# luci2_device_revA.net
KiCad netlist of a schematic drawn in EAGLE
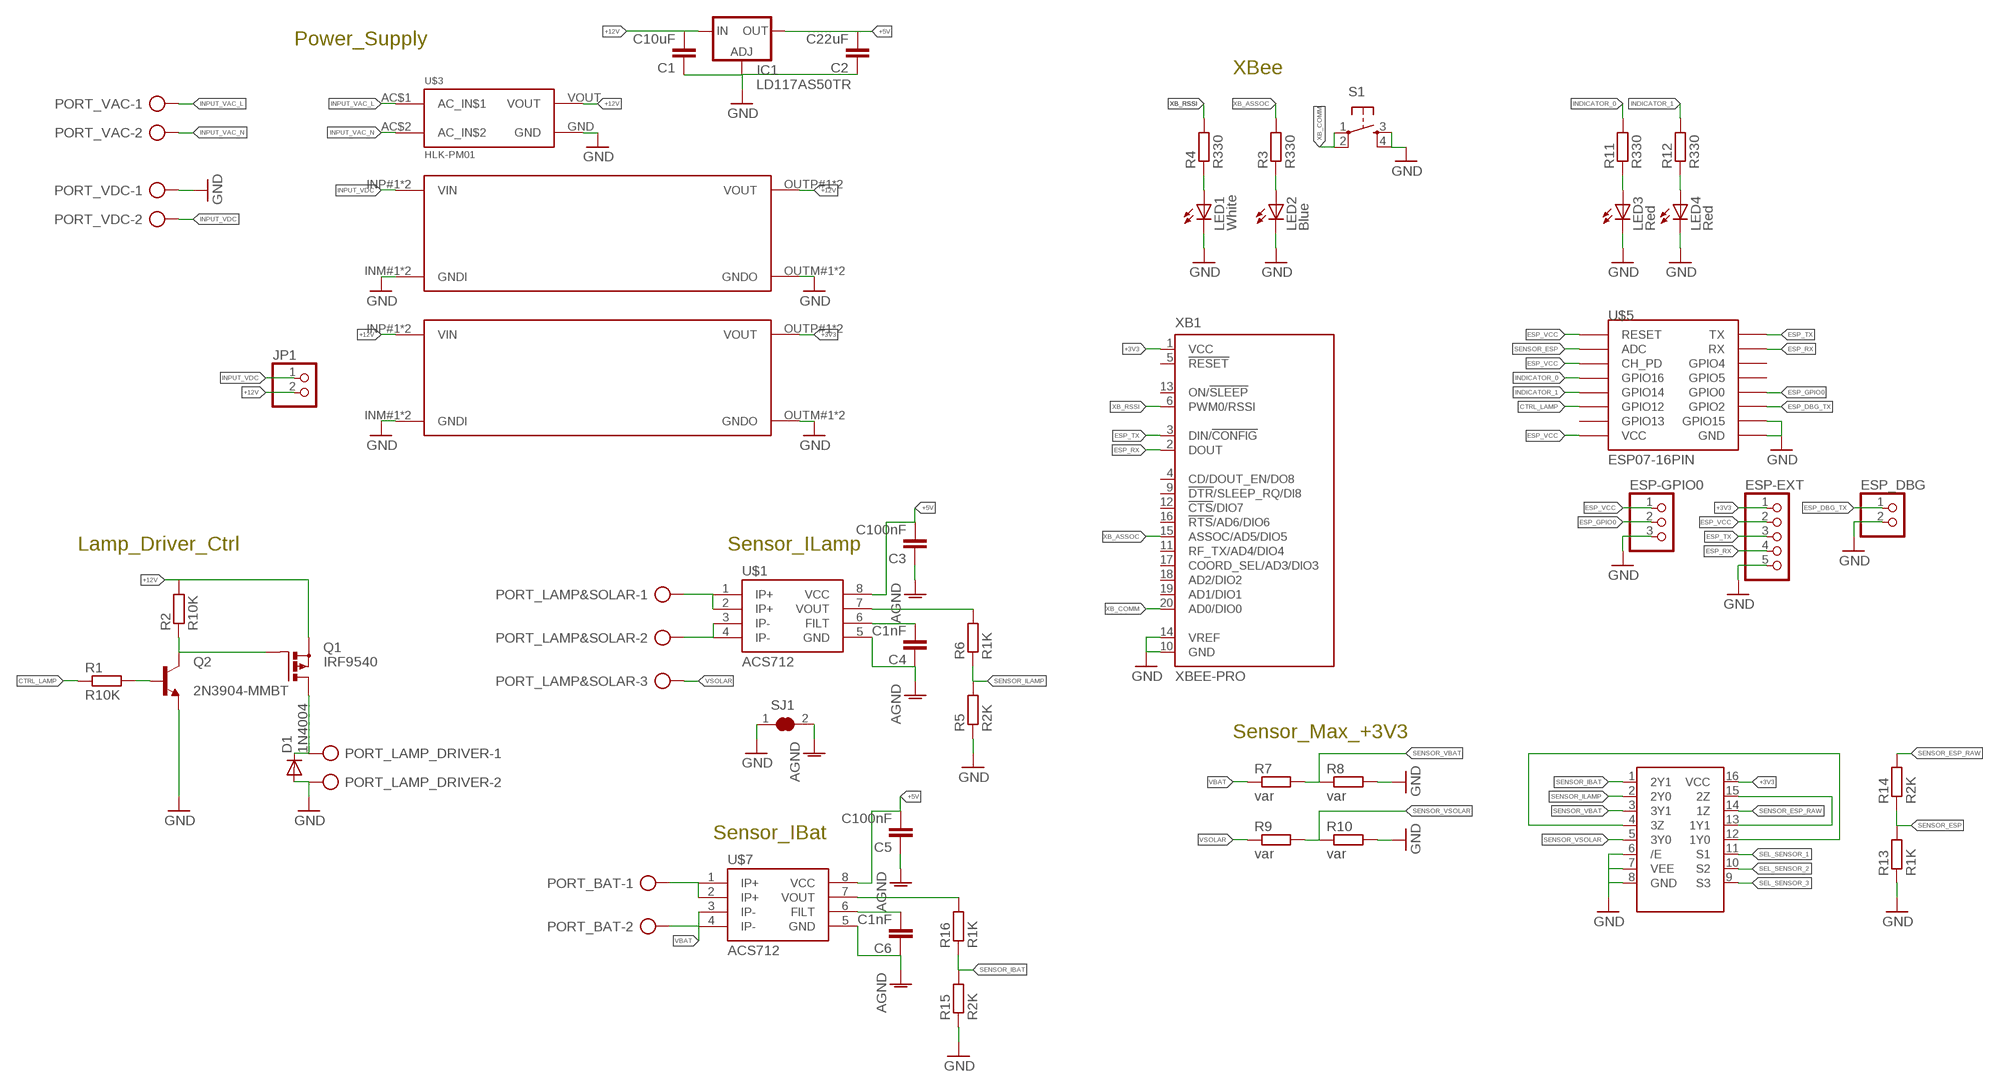
[diagram p0: schematic, sheet 1]

(export (version "E")
  (design (tool "Eeschema 10.0.6"))
  (components
    (comp (ref "C1")
      (value "C10uF")
      (footprint "eagle-import:C0805")
      (libsource (lib "eagle-import") (part "C-EUC0805"))
    )
    (comp (ref "C2")
      (value "C22uF")
      (footprint "eagle-import:C0805")
      (libsource (lib "eagle-import") (part "C-EUC0805"))
    )
    (comp (ref "C3")
      (value "C100nF")
      (footprint "eagle-import:C0805")
      (libsource (lib "eagle-import") (part "C-EUC0805"))
    )
    (comp (ref "C4")
      (value "C1nF")
      (footprint "eagle-import:C0805")
      (libsource (lib "eagle-import") (part "C-EUC0805"))
    )
    (comp (ref "C5")
      (value "C100nF")
      (footprint "eagle-import:C0805")
      (libsource (lib "eagle-import") (part "C-EUC0805"))
    )
    (comp (ref "C6")
      (value "C1nF")
      (footprint "eagle-import:C0805")
      (libsource (lib "eagle-import") (part "C-EUC0805"))
    )
    (comp (ref "D1")
      (value "1N4004")
      (footprint "eagle-import:DO41-10")
      (libsource (lib "eagle-import") (part "1N4004"))
    )
    (comp (ref "ESP-EXT")
      (value "HEADER-1X5ROUND")
      (footprint "eagle-import:1X05_ROUND")
      (libsource (lib "eagle-import") (part "HEADER-1X5ROUND"))
    )
    (comp (ref "ESP-GPIO0")
      (value "HEADER-1X3ROUND")
      (footprint "eagle-import:1X03_ROUND")
      (libsource (lib "eagle-import") (part "HEADER-1X3ROUND"))
    )
    (comp (ref "ESP_DBG")
      (value "HEADER-1X2ROUND")
      (footprint "eagle-import:1X02_ROUND")
      (libsource (lib "eagle-import") (part "HEADER-1X2ROUND"))
    )
    (comp (ref "IC1")
      (value "LD117AS50TR")
      (footprint "eagle-import:SOT223")
      (libsource (lib "eagle-import") (part "LD117A?S50TR"))
    )
    (comp (ref "JP1")
      (value "HEADER-1X2ROUND")
      (footprint "eagle-import:1X02_ROUND")
      (libsource (lib "eagle-import") (part "HEADER-1X2ROUND"))
    )
    (comp (ref "LED1")
      (value "White")
      (footprint "eagle-import:CHIPLED_0805")
      (libsource (lib "eagle-import") (part "LEDCHIPLED_0805"))
    )
    (comp (ref "LED2")
      (value "Blue")
      (footprint "eagle-import:CHIPLED_0805")
      (libsource (lib "eagle-import") (part "LEDCHIPLED_0805"))
    )
    (comp (ref "LED3")
      (value "Red")
      (footprint "eagle-import:CHIPLED_0805")
      (libsource (lib "eagle-import") (part "LEDCHIPLED_0805"))
    )
    (comp (ref "LED4")
      (value "Red")
      (footprint "eagle-import:CHIPLED_0805")
      (libsource (lib "eagle-import") (part "LEDCHIPLED_0805"))
    )
    (comp (ref "PORT_BAT")
      (value "AK300/2")
      (footprint "eagle-import:AK300_2")
      (libsource (lib "eagle-import") (part "AK300/2"))
    )
    (comp (ref "PORT_LAMP&SOLAR")
      (value "AK300/3")
      (footprint "eagle-import:AK300_3")
      (libsource (lib "eagle-import") (part "AK300/3"))
    )
    (comp (ref "PORT_LAMP_DRIVER")
      (value "AK300/2")
      (footprint "eagle-import:AK300_2")
      (libsource (lib "eagle-import") (part "AK300/2"))
    )
    (comp (ref "PORT_VAC")
      (value "AK300/2")
      (footprint "eagle-import:AK300_2")
      (libsource (lib "eagle-import") (part "AK300/2"))
    )
    (comp (ref "PORT_VDC")
      (value "AK300/2")
      (footprint "eagle-import:AK300_2")
      (libsource (lib "eagle-import") (part "AK300/2"))
    )
    (comp (ref "Q1")
      (value "IRF9540")
      (footprint "eagle-import:TO220BV")
      (libsource (lib "eagle-import") (part "PMOSFET_PTO220BV"))
    )
    (comp (ref "Q2")
      (value "2N3904-MMBT")
      (footprint "eagle-import:SOT23")
      (libsource (lib "eagle-import") (part "2N3904-MMBT"))
    )
    (comp (ref "R1")
      (value "R10K")
      (footprint "eagle-import:M0805")
      (libsource (lib "eagle-import") (part "R-EU_M0805"))
    )
    (comp (ref "R2")
      (value "R10K")
      (footprint "eagle-import:M0805")
      (libsource (lib "eagle-import") (part "R-EU_M0805"))
    )
    (comp (ref "R3")
      (value "R330")
      (footprint "eagle-import:M0805")
      (libsource (lib "eagle-import") (part "R-EU_M0805"))
    )
    (comp (ref "R4")
      (value "R330")
      (footprint "eagle-import:M0805")
      (libsource (lib "eagle-import") (part "R-EU_M0805"))
    )
    (comp (ref "R5")
      (value "R2K")
      (footprint "eagle-import:M0805")
      (libsource (lib "eagle-import") (part "R-EU_M0805"))
    )
    (comp (ref "R6")
      (value "R1K")
      (footprint "eagle-import:M0805")
      (libsource (lib "eagle-import") (part "R-EU_M0805"))
    )
    (comp (ref "R7")
      (value "var")
      (footprint "eagle-import:M0805")
      (libsource (lib "eagle-import") (part "R-EU_M0805"))
    )
    (comp (ref "R8")
      (value "var")
      (footprint "eagle-import:M0805")
      (libsource (lib "eagle-import") (part "R-EU_M0805"))
    )
    (comp (ref "R9")
      (value "var")
      (footprint "eagle-import:M0805")
      (libsource (lib "eagle-import") (part "R-EU_M0805"))
    )
    (comp (ref "R10")
      (value "var")
      (footprint "eagle-import:M0805")
      (libsource (lib "eagle-import") (part "R-EU_M0805"))
    )
    (comp (ref "R11")
      (value "R330")
      (footprint "eagle-import:M0805")
      (libsource (lib "eagle-import") (part "R-EU_M0805"))
    )
    (comp (ref "R12")
      (value "R330")
      (footprint "eagle-import:M0805")
      (libsource (lib "eagle-import") (part "R-EU_M0805"))
    )
    (comp (ref "R13")
      (value "R1K")
      (footprint "eagle-import:M0805")
      (libsource (lib "eagle-import") (part "R-EU_M0805"))
    )
    (comp (ref "R14")
      (value "R2K")
      (footprint "eagle-import:M0805")
      (libsource (lib "eagle-import") (part "R-EU_M0805"))
    )
    (comp (ref "R15")
      (value "R2K")
      (footprint "eagle-import:M0805")
      (libsource (lib "eagle-import") (part "R-EU_M0805"))
    )
    (comp (ref "R16")
      (value "R1K")
      (footprint "eagle-import:M0805")
      (libsource (lib "eagle-import") (part "R-EU_M0805"))
    )
    (comp (ref "S1")
      (value "TAC_SWITCHPTH")
      (footprint "eagle-import:TACTILE-PTH")
      (libsource (lib "eagle-import") (part "TAC_SWITCHPTH"))
    )
    (comp (ref "SJ1")
      (value "SOLDERJUMPER_CLOSED")
      (footprint "eagle-import:SOLDERJUMPER_CLOSEDWIRE")
      (libsource (lib "eagle-import") (part "SOLDERJUMPER_CLOSED"))
    )
    (comp (ref "U$1")
      (value "ACS712")
      (footprint "eagle-import:SO08")
      (libsource (lib "eagle-import") (part "ACS712"))
    )
    (comp (ref "U$2")
      (value "DCDCMODULE_SMALL")
      (footprint "eagle-import:DCDCMODULE-SMALL")
      (libsource (lib "eagle-import") (part "DCDCMODULE_SMALL"))
    )
    (comp (ref "U$3")
      (value "HLK-PM01")
      (footprint "eagle-import:HLK-PM01")
      (libsource (lib "eagle-import") (part "HLK-PM01"))
    )
    (comp (ref "U$4")
      (value "DCDCMODULE_SMALL")
      (footprint "eagle-import:DCDCMODULE-SMALL")
      (libsource (lib "eagle-import") (part "DCDCMODULE_SMALL"))
    )
    (comp (ref "U$5")
      (value "ESP07-16PIN")
      (footprint "eagle-import:ESP07-16PIN")
      (libsource (lib "eagle-import") (part "ESP07-16PIN"))
    )
    (comp (ref "U$6")
      (value "74HC4053D")
      (footprint "eagle-import:SO16")
      (libsource (lib "eagle-import") (part "74HC4053D"))
    )
    (comp (ref "U$7")
      (value "ACS712")
      (footprint "eagle-import:SO08")
      (libsource (lib "eagle-import") (part "ACS712"))
    )
    (comp (ref "XB1")
      (value "XBEE-PRO")
      (footprint "eagle-import:XBEE-PRO")
      (libsource (lib "eagle-import") (part "XBEE-PRO"))
    )
  )
  (nets
    (net (code "1") (name "+3V3") (class "Default")
      (node (ref "ESP-EXT") (pin "1") (pinfunction "1_1") (pintype "passive"))
      (node (ref "U$2") (pin "OUTP#1") (pinfunction "VOUT_OUTP#1") (pintype "bidirectional"))
      (node (ref "U$2") (pin "OUTP#2") (pinfunction "VOUT_OUTP#2") (pintype "bidirectional"))
      (node (ref "U$6") (pin "16") (pinfunction "VCC_16") (pintype "bidirectional"))
      (node (ref "XB1") (pin "1") (pinfunction "VCC_1") (pintype "power_in"))
    )
    (net (code "2") (name "+5V") (class "Default")
      (node (ref "C2") (pin "2") (pinfunction "2_2") (pintype "passive"))
      (node (ref "C3") (pin "2") (pinfunction "2_2") (pintype "passive"))
      (node (ref "C5") (pin "2") (pinfunction "2_2") (pintype "passive"))
      (node (ref "IC1") (pin "4") (pinfunction "OUT_4") (pintype "passive"))
      (node (ref "U$1") (pin "8") (pinfunction "VCC_8") (pintype "bidirectional"))
      (node (ref "U$7") (pin "8") (pinfunction "VCC_8") (pintype "bidirectional"))
    )
    (net (code "3") (name "+12V") (class "Default")
      (node (ref "C1") (pin "2") (pinfunction "2_2") (pintype "passive"))
      (node (ref "IC1") (pin "3") (pinfunction "IN_3") (pintype "input"))
      (node (ref "JP1") (pin "2") (pinfunction "2_2") (pintype "passive"))
      (node (ref "Q1") (pin "S") (pinfunction "S_S") (pintype "passive"))
      (node (ref "R2") (pin "2") (pinfunction "2_2") (pintype "passive"))
      (node (ref "U$2") (pin "INP#1") (pinfunction "VIN_INP#1") (pintype "bidirectional"))
      (node (ref "U$2") (pin "INP#2") (pinfunction "VIN_INP#2") (pintype "bidirectional"))
      (node (ref "U$3") (pin "VOUT") (pinfunction "VOUT_VOUT") (pintype "bidirectional"))
      (node (ref "U$4") (pin "OUTP#1") (pinfunction "VOUT_OUTP#1") (pintype "bidirectional"))
      (node (ref "U$4") (pin "OUTP#2") (pinfunction "VOUT_OUTP#2") (pintype "bidirectional"))
    )
    (net (code "4") (name "AGND") (class "Default")
      (node (ref "C3") (pin "1") (pinfunction "1_1") (pintype "passive"))
      (node (ref "C4") (pin "1") (pinfunction "1_1") (pintype "passive"))
      (node (ref "C5") (pin "1") (pinfunction "1_1") (pintype "passive"))
      (node (ref "C6") (pin "1") (pinfunction "1_1") (pintype "passive"))
      (node (ref "SJ1") (pin "2") (pinfunction "2_2") (pintype "passive"))
      (node (ref "U$1") (pin "5") (pinfunction "GND_5") (pintype "bidirectional"))
      (node (ref "U$7") (pin "5") (pinfunction "GND_5") (pintype "bidirectional"))
    )
    (net (code "5") (name "CTRL_LAMP") (class "Default")
      (node (ref "R1") (pin "1") (pinfunction "1_1") (pintype "passive"))
      (node (ref "U$5") (pin "GPIO12") (pinfunction "GPIO12_GPIO12") (pintype "bidirectional"))
    )
    (net (code "6") (name "ESP_DBG_TX") (class "Default")
      (node (ref "ESP_DBG") (pin "1") (pinfunction "1_1") (pintype "passive"))
      (node (ref "U$5") (pin "GPIO2") (pinfunction "GPIO2_GPIO2") (pintype "bidirectional"))
    )
    (net (code "7") (name "ESP_GPIO0") (class "Default")
      (node (ref "ESP-GPIO0") (pin "2") (pinfunction "2_2") (pintype "passive"))
      (node (ref "U$5") (pin "GPIO0") (pinfunction "GPIO0_GPIO0") (pintype "bidirectional"))
    )
    (net (code "8") (name "ESP_RX") (class "Default")
      (node (ref "ESP-EXT") (pin "4") (pinfunction "4_4") (pintype "passive"))
      (node (ref "U$5") (pin "RX") (pinfunction "RX_RX") (pintype "bidirectional"))
      (node (ref "XB1") (pin "2") (pinfunction "DOUT_2") (pintype "output"))
    )
    (net (code "9") (name "ESP_TX") (class "Default")
      (node (ref "ESP-EXT") (pin "3") (pinfunction "3_3") (pintype "passive"))
      (node (ref "U$5") (pin "TX") (pinfunction "TX_TX") (pintype "bidirectional"))
      (node (ref "XB1") (pin "3") (pinfunction "DIN/~{CONFIG}_3") (pintype "input"))
    )
    (net (code "10") (name "ESP_VCC") (class "Default")
      (node (ref "ESP-EXT") (pin "2") (pinfunction "2_2") (pintype "passive"))
      (node (ref "ESP-GPIO0") (pin "1") (pinfunction "1_1") (pintype "passive"))
      (node (ref "U$5") (pin "CH_PD") (pinfunction "CH_PD_CH_PD") (pintype "bidirectional"))
      (node (ref "U$5") (pin "REST") (pinfunction "RESET_REST") (pintype "bidirectional"))
      (node (ref "U$5") (pin "VCC") (pinfunction "VCC_VCC") (pintype "bidirectional"))
    )
    (net (code "11") (name "GND") (class "Default")
      (node (ref "C1") (pin "1") (pinfunction "1_1") (pintype "passive"))
      (node (ref "C2") (pin "1") (pinfunction "1_1") (pintype "passive"))
      (node (ref "D1") (pin "A") (pinfunction "A_A") (pintype "passive"))
      (node (ref "ESP-EXT") (pin "5") (pinfunction "5_5") (pintype "passive"))
      (node (ref "ESP-GPIO0") (pin "3") (pinfunction "3_3") (pintype "passive"))
      (node (ref "ESP_DBG") (pin "2") (pinfunction "2_2") (pintype "passive"))
      (node (ref "IC1") (pin "1") (pinfunction "ADJ_1") (pintype "input"))
      (node (ref "LED1") (pin "C") (pinfunction "C_C") (pintype "passive"))
      (node (ref "LED2") (pin "C") (pinfunction "C_C") (pintype "passive"))
      (node (ref "LED3") (pin "C") (pinfunction "C_C") (pintype "passive"))
      (node (ref "LED4") (pin "C") (pinfunction "C_C") (pintype "passive"))
      (node (ref "PORT_LAMP_DRIVER") (pin "2") (pinfunction "KL_2") (pintype "passive"))
      (node (ref "PORT_VDC") (pin "1") (pinfunction "KL_1") (pintype "passive"))
      (node (ref "Q2") (pin "2") (pinfunction "E_2") (pintype "passive"))
      (node (ref "R10") (pin "2") (pinfunction "2_2") (pintype "passive"))
      (node (ref "R13") (pin "1") (pinfunction "1_1") (pintype "passive"))
      (node (ref "R15") (pin "1") (pinfunction "1_1") (pintype "passive"))
      (node (ref "R5") (pin "1") (pinfunction "1_1") (pintype "passive"))
      (node (ref "R8") (pin "2") (pinfunction "2_2") (pintype "passive"))
      (node (ref "S1") (pin "3") (pinfunction "3_3") (pintype "passive"))
      (node (ref "S1") (pin "4") (pinfunction "4_4") (pintype "passive"))
      (node (ref "SJ1") (pin "1") (pinfunction "1_1") (pintype "passive"))
      (node (ref "U$2") (pin "INM#1") (pinfunction "GNDI_INM#1") (pintype "bidirectional"))
      (node (ref "U$2") (pin "INM#2") (pinfunction "GNDI_INM#2") (pintype "bidirectional"))
      (node (ref "U$2") (pin "OUTM#1") (pinfunction "GNDO_OUTM#1") (pintype "bidirectional"))
      (node (ref "U$2") (pin "OUTM#2") (pinfunction "GNDO_OUTM#2") (pintype "bidirectional"))
      (node (ref "U$3") (pin "GND") (pinfunction "GND_GND") (pintype "bidirectional"))
      (node (ref "U$4") (pin "INM#1") (pinfunction "GNDI_INM#1") (pintype "bidirectional"))
      (node (ref "U$4") (pin "INM#2") (pinfunction "GNDI_INM#2") (pintype "bidirectional"))
      (node (ref "U$4") (pin "OUTM#1") (pinfunction "GNDO_OUTM#1") (pintype "bidirectional"))
      (node (ref "U$4") (pin "OUTM#2") (pinfunction "GNDO_OUTM#2") (pintype "bidirectional"))
      (node (ref "U$5") (pin "GND") (pinfunction "GND_GND") (pintype "bidirectional"))
      (node (ref "U$5") (pin "GPIO15") (pinfunction "GPIO15_GPIO15") (pintype "bidirectional"))
      (node (ref "U$6") (pin "6") (pinfunction "/E_6") (pintype "bidirectional"))
      (node (ref "U$6") (pin "7") (pinfunction "VEE_7") (pintype "bidirectional"))
      (node (ref "U$6") (pin "8") (pinfunction "GND_8") (pintype "bidirectional"))
      (node (ref "XB1") (pin "10") (pinfunction "GND_10") (pintype "power_in"))
      (node (ref "XB1") (pin "14") (pinfunction "VREF_14") (pintype "input"))
    )
    (net (code "12") (name "INDICATOR_0") (class "Default")
      (node (ref "R11") (pin "2") (pinfunction "2_2") (pintype "passive"))
      (node (ref "U$5") (pin "GPIO16") (pinfunction "GPIO16_GPIO16") (pintype "bidirectional"))
    )
    (net (code "13") (name "INDICATOR_1") (class "Default")
      (node (ref "R12") (pin "2") (pinfunction "2_2") (pintype "passive"))
      (node (ref "U$5") (pin "GPIO14") (pinfunction "GPIO14_GPIO14") (pintype "bidirectional"))
    )
    (net (code "14") (name "INPUT_VAC_L") (class "Default")
      (node (ref "PORT_VAC") (pin "1") (pinfunction "KL_1") (pintype "passive"))
      (node (ref "U$3") (pin "AC$1") (pinfunction "AC_IN$1_AC$1") (pintype "bidirectional"))
    )
    (net (code "15") (name "INPUT_VAC_N") (class "Default")
      (node (ref "PORT_VAC") (pin "2") (pinfunction "KL_2") (pintype "passive"))
      (node (ref "U$3") (pin "AC$2") (pinfunction "AC_IN$2_AC$2") (pintype "bidirectional"))
    )
    (net (code "16") (name "INPUT_VDC") (class "Default")
      (node (ref "JP1") (pin "1") (pinfunction "1_1") (pintype "passive"))
      (node (ref "PORT_VDC") (pin "2") (pinfunction "KL_2") (pintype "passive"))
      (node (ref "U$4") (pin "INP#1") (pinfunction "VIN_INP#1") (pintype "bidirectional"))
      (node (ref "U$4") (pin "INP#2") (pinfunction "VIN_INP#2") (pintype "bidirectional"))
    )
    (net (code "17") (name "Net-(LED1-PadA)") (class "Default")
      (node (ref "LED1") (pin "A") (pinfunction "A_A") (pintype "passive"))
      (node (ref "R4") (pin "1") (pinfunction "1_1") (pintype "passive"))
    )
    (net (code "18") (name "Net-(LED2-PadA)") (class "Default")
      (node (ref "LED2") (pin "A") (pinfunction "A_A") (pintype "passive"))
      (node (ref "R3") (pin "1") (pinfunction "1_1") (pintype "passive"))
    )
    (net (code "19") (name "Net-(LED3-PadA)") (class "Default")
      (node (ref "LED3") (pin "A") (pinfunction "A_A") (pintype "passive"))
      (node (ref "R11") (pin "1") (pinfunction "1_1") (pintype "passive"))
    )
    (net (code "20") (name "Net-(LED4-PadA)") (class "Default")
      (node (ref "LED4") (pin "A") (pinfunction "A_A") (pintype "passive"))
      (node (ref "R12") (pin "1") (pinfunction "1_1") (pintype "passive"))
    )
    (net (code "21") (name "Net-(PORT_BATA-KL)") (class "Default")
      (node (ref "PORT_BAT") (pin "1") (pinfunction "KL_1") (pintype "passive"))
      (node (ref "U$7") (pin "1") (pinfunction "IP+_1") (pintype "bidirectional"))
      (node (ref "U$7") (pin "2") (pinfunction "IP+_2") (pintype "bidirectional"))
    )
    (net (code "22") (name "Net-(PORT_LAMP&SOLARA-KL)") (class "Default")
      (node (ref "PORT_LAMP&SOLAR") (pin "1") (pinfunction "KL_1") (pintype "passive"))
      (node (ref "U$1") (pin "1") (pinfunction "IP+_1") (pintype "bidirectional"))
      (node (ref "U$1") (pin "2") (pinfunction "IP+_2") (pintype "bidirectional"))
    )
    (net (code "23") (name "Net-(PORT_LAMP&SOLARB-KL)") (class "Default")
      (node (ref "PORT_LAMP&SOLAR") (pin "2") (pinfunction "KL_2") (pintype "passive"))
      (node (ref "U$1") (pin "3") (pinfunction "IP-_3") (pintype "bidirectional"))
      (node (ref "U$1") (pin "4") (pinfunction "IP-_4") (pintype "bidirectional"))
    )
    (net (code "24") (name "Net-(PORT_LAMP_DRIVERA-KL)") (class "Default")
      (node (ref "D1") (pin "C") (pinfunction "C_C") (pintype "passive"))
      (node (ref "PORT_LAMP_DRIVER") (pin "1") (pinfunction "KL_1") (pintype "passive"))
      (node (ref "Q1") (pin "D") (pinfunction "D_D") (pintype "passive"))
    )
    (net (code "25") (name "Net-(Q2-B)") (class "Default")
      (node (ref "Q2") (pin "1") (pinfunction "B_1") (pintype "passive"))
      (node (ref "R1") (pin "2") (pinfunction "2_2") (pintype "passive"))
    )
    (net (code "26") (name "Net-(Q2-C)") (class "Default")
      (node (ref "Q1") (pin "G") (pinfunction "G_G") (pintype "passive"))
      (node (ref "Q2") (pin "3") (pinfunction "C_3") (pintype "passive"))
      (node (ref "R2") (pin "1") (pinfunction "1_1") (pintype "passive"))
    )
    (net (code "27") (name "Net-(U$1-FILT)") (class "Default")
      (node (ref "C4") (pin "2") (pinfunction "2_2") (pintype "passive"))
      (node (ref "U$1") (pin "6") (pinfunction "FILT_6") (pintype "bidirectional"))
    )
    (net (code "28") (name "Net-(U$1-VOUT)") (class "Default")
      (node (ref "R6") (pin "2") (pinfunction "2_2") (pintype "passive"))
      (node (ref "U$1") (pin "7") (pinfunction "VOUT_7") (pintype "bidirectional"))
    )
    (net (code "29") (name "Net-(U$6-1Y0)") (class "Default")
      (node (ref "U$6") (pin "12") (pinfunction "1Y0_12") (pintype "bidirectional"))
      (node (ref "U$6") (pin "4") (pinfunction "3Z_4") (pintype "bidirectional"))
    )
    (net (code "30") (name "Net-(U$6-1Y1)") (class "Default")
      (node (ref "U$6") (pin "13") (pinfunction "1Y1_13") (pintype "bidirectional"))
      (node (ref "U$6") (pin "15") (pinfunction "2Z_15") (pintype "bidirectional"))
    )
    (net (code "31") (name "Net-(U$7-FILT)") (class "Default")
      (node (ref "C6") (pin "2") (pinfunction "2_2") (pintype "passive"))
      (node (ref "U$7") (pin "6") (pinfunction "FILT_6") (pintype "bidirectional"))
    )
    (net (code "32") (name "Net-(U$7-VOUT)") (class "Default")
      (node (ref "R16") (pin "2") (pinfunction "2_2") (pintype "passive"))
      (node (ref "U$7") (pin "7") (pinfunction "VOUT_7") (pintype "bidirectional"))
    )
    (net (code "33") (name "SEL_SENSOR_1") (class "Default")
      (node (ref "U$6") (pin "11") (pinfunction "S1_11") (pintype "bidirectional"))
    )
    (net (code "34") (name "SEL_SENSOR_2") (class "Default")
      (node (ref "U$6") (pin "10") (pinfunction "S2_10") (pintype "bidirectional"))
    )
    (net (code "35") (name "SEL_SENSOR_3") (class "Default")
      (node (ref "U$6") (pin "9") (pinfunction "S3_9") (pintype "bidirectional"))
    )
    (net (code "36") (name "SENSOR_ESP") (class "Default")
      (node (ref "R13") (pin "2") (pinfunction "2_2") (pintype "passive"))
      (node (ref "R14") (pin "1") (pinfunction "1_1") (pintype "passive"))
      (node (ref "U$5") (pin "ADC") (pinfunction "ADC_ADC") (pintype "bidirectional"))
    )
    (net (code "37") (name "SENSOR_ESP_RAW") (class "Default")
      (node (ref "R14") (pin "2") (pinfunction "2_2") (pintype "passive"))
      (node (ref "U$6") (pin "14") (pinfunction "1Z_14") (pintype "bidirectional"))
    )
    (net (code "38") (name "SENSOR_IBAT") (class "Default")
      (node (ref "R15") (pin "2") (pinfunction "2_2") (pintype "passive"))
      (node (ref "R16") (pin "1") (pinfunction "1_1") (pintype "passive"))
      (node (ref "U$6") (pin "1") (pinfunction "2Y1_1") (pintype "bidirectional"))
    )
    (net (code "39") (name "SENSOR_ILAMP") (class "Default")
      (node (ref "R5") (pin "2") (pinfunction "2_2") (pintype "passive"))
      (node (ref "R6") (pin "1") (pinfunction "1_1") (pintype "passive"))
      (node (ref "U$6") (pin "2") (pinfunction "2Y0_2") (pintype "bidirectional"))
    )
    (net (code "40") (name "SENSOR_VBAT") (class "Default")
      (node (ref "R7") (pin "2") (pinfunction "2_2") (pintype "passive"))
      (node (ref "R8") (pin "1") (pinfunction "1_1") (pintype "passive"))
      (node (ref "U$6") (pin "3") (pinfunction "3Y1_3") (pintype "bidirectional"))
    )
    (net (code "41") (name "SENSOR_VSOLAR") (class "Default")
      (node (ref "R10") (pin "1") (pinfunction "1_1") (pintype "passive"))
      (node (ref "R9") (pin "2") (pinfunction "2_2") (pintype "passive"))
      (node (ref "U$6") (pin "5") (pinfunction "3Y0_5") (pintype "bidirectional"))
    )
    (net (code "42") (name "VBAT") (class "Default")
      (node (ref "PORT_BAT") (pin "2") (pinfunction "KL_2") (pintype "passive"))
      (node (ref "R7") (pin "1") (pinfunction "1_1") (pintype "passive"))
      (node (ref "U$7") (pin "3") (pinfunction "IP-_3") (pintype "bidirectional"))
      (node (ref "U$7") (pin "4") (pinfunction "IP-_4") (pintype "bidirectional"))
    )
    (net (code "43") (name "VSOLAR") (class "Default")
      (node (ref "PORT_LAMP&SOLAR") (pin "3") (pinfunction "KL_3") (pintype "passive"))
      (node (ref "R9") (pin "1") (pinfunction "1_1") (pintype "passive"))
    )
    (net (code "44") (name "XB_ASSOC") (class "Default")
      (node (ref "R3") (pin "2") (pinfunction "2_2") (pintype "passive"))
      (node (ref "XB1") (pin "15") (pinfunction "ASSOC/AD5/DIO5_15") (pintype "bidirectional"))
    )
    (net (code "45") (name "XB_COMM") (class "Default")
      (node (ref "S1") (pin "1") (pinfunction "1_1") (pintype "passive"))
      (node (ref "S1") (pin "2") (pinfunction "2_2") (pintype "passive"))
      (node (ref "XB1") (pin "20") (pinfunction "AD0/DIO0_20") (pintype "bidirectional"))
    )
    (net (code "46") (name "XB_RSSI") (class "Default")
      (node (ref "R4") (pin "2") (pinfunction "2_2") (pintype "passive"))
      (node (ref "XB1") (pin "6") (pinfunction "PWM0/RSSI_6") (pintype "output"))
    )
    (net (code "47") (name "unconnected-(U$5-PadGPIO4)") (class "Default")
      (node (ref "U$5") (pin "GPIO4") (pinfunction "GPIO4_GPIO4") (pintype "bidirectional"))
    )
    (net (code "48") (name "unconnected-(U$5-PadGPIO5)") (class "Default")
      (node (ref "U$5") (pin "GPIO5") (pinfunction "GPIO5_GPIO5") (pintype "bidirectional"))
    )
    (net (code "49") (name "unconnected-(U$5-PadGPIO13)") (class "Default")
      (node (ref "U$5") (pin "GPIO13") (pinfunction "GPIO13_GPIO13") (pintype "bidirectional"))
    )
    (net (code "50") (name "unconnected-(XB1-AD1{slash}DIO1-Pad19)") (class "Default")
      (node (ref "XB1") (pin "19") (pinfunction "AD1/DIO1_19") (pintype "bidirectional"))
    )
    (net (code "51") (name "unconnected-(XB1-AD2{slash}DIO2-Pad18)") (class "Default")
      (node (ref "XB1") (pin "18") (pinfunction "AD2/DIO2_18") (pintype "bidirectional"))
    )
    (net (code "52") (name "unconnected-(XB1-CD{slash}DOUT_EN{slash}DO8-Pad4)") (class "Default")
      (node (ref "XB1") (pin "4") (pinfunction "CD/DOUT_EN/DO8_4") (pintype "output"))
    )
    (net (code "53") (name "unconnected-(XB1-COORD_SEL{slash}AD3{slash}DIO3-Pad17)") (class "Default")
      (node (ref "XB1") (pin "17") (pinfunction "COORD_SEL/AD3/DIO3_17") (pintype "bidirectional"))
    )
    (net (code "54") (name "unconnected-(XB1-ON{slash}~{SLEEP}-Pad13)") (class "Default")
      (node (ref "XB1") (pin "13") (pinfunction "ON/~{SLEEP}_13") (pintype "output"))
    )
    (net (code "55") (name "unconnected-(XB1-RF_TX{slash}AD4{slash}DIO4-Pad11)") (class "Default")
      (node (ref "XB1") (pin "11") (pinfunction "RF_TX/AD4/DIO4_11") (pintype "bidirectional"))
    )
    (net (code "56") (name "unconnected-(XB1-~{CTS}{slash}DIO7-Pad12)") (class "Default")
      (node (ref "XB1") (pin "12") (pinfunction "~{CTS}/DIO7_12") (pintype "bidirectional"))
    )
    (net (code "57") (name "unconnected-(XB1-~{DTR}{slash}SLEEP_RQ{slash}DI8-Pad9)") (class "Default")
      (node (ref "XB1") (pin "9") (pinfunction "~{DTR}/SLEEP_RQ/DI8_9") (pintype "bidirectional"))
    )
    (net (code "58") (name "unconnected-(XB1-~{RESET}-Pad5)") (class "Default")
      (node (ref "XB1") (pin "5") (pinfunction "~{RESET}_5") (pintype "input"))
    )
    (net (code "59") (name "unconnected-(XB1-~{RTS}{slash}AD6{slash}DIO6-Pad16)") (class "Default")
      (node (ref "XB1") (pin "16") (pinfunction "~{RTS}/AD6/DIO6_16") (pintype "bidirectional"))
    )
  )
)
